# DRV8701.net
KiCad netlist of a schematic drawn in EasyEDA Pro
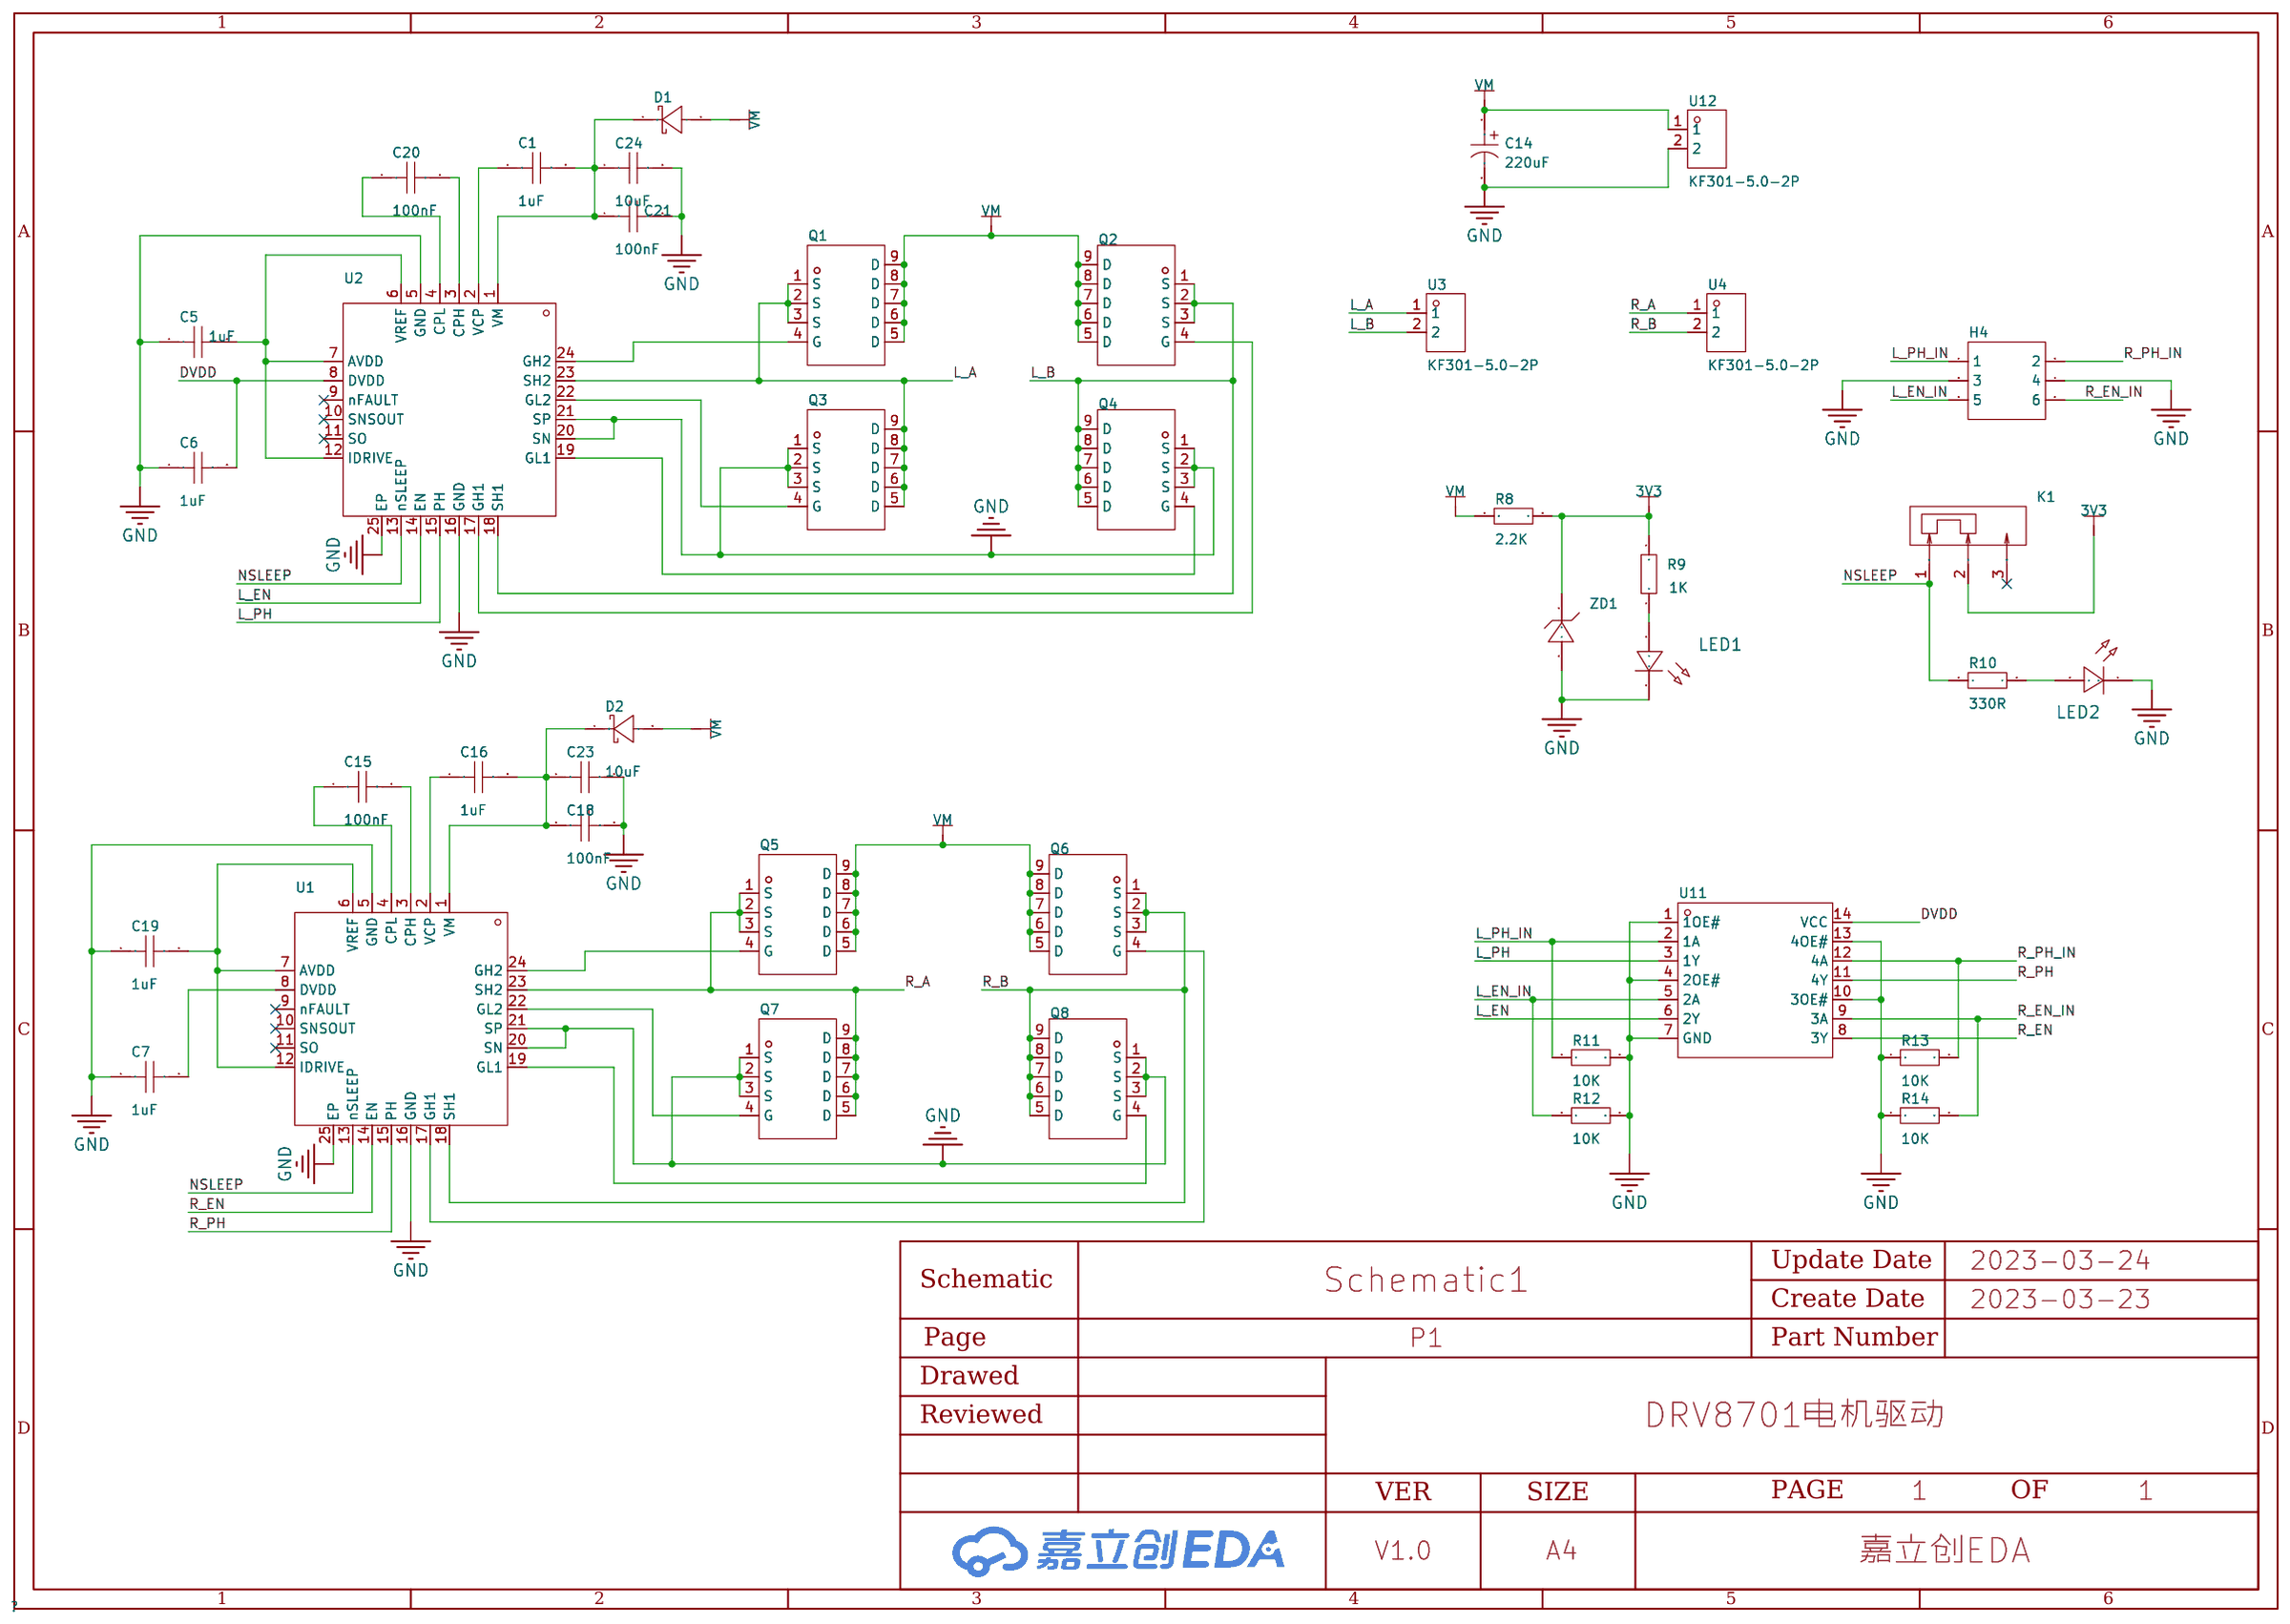
[diagram p0: schematic sheet]

(export (version "E")
  (design (tool "Eeschema 10.0.6"))
  (components
    (comp (ref "C1")
      (value "1uF")
      (footprint "easyedapro:C0805")
      (libsource (lib "easyedapro") (part "CapAcitance"))
    )
    (comp (ref "C5")
      (value "1uF")
      (footprint "easyedapro:C0805")
      (libsource (lib "easyedapro") (part "CapAcitance"))
    )
    (comp (ref "C6")
      (value "1uF")
      (footprint "easyedapro:C0805")
      (libsource (lib "easyedapro") (part "CapAcitance"))
    )
    (comp (ref "C7")
      (value "1uF")
      (footprint "easyedapro:C0805")
      (libsource (lib "easyedapro") (part "CapAcitance"))
    )
    (comp (ref "C14")
      (value "220uF")
      (footprint "easyedapro:CAP-SMD_BD6.3-L6.6-W6.6-LS7.2-FD")
      (fields
        (field (name "Manufacturer Part") "MVG 16V 220UF 6.3*7.7")
        (field (name "Manufacturer") "SAMYOUNG(韩国三莹)")
        (field (name "Tolerance") "±20%")
      )
      (libsource (lib "easyedapro") (part "MVG 16V 220UF 6.3*7.7"))
    )
    (comp (ref "C15")
      (value "100nF")
      (footprint "easyedapro:C0805")
      (libsource (lib "easyedapro") (part "CapAcitance"))
    )
    (comp (ref "C16")
      (value "1uF")
      (footprint "easyedapro:C0805")
      (libsource (lib "easyedapro") (part "CapAcitance"))
    )
    (comp (ref "C18")
      (value "100nF")
      (footprint "easyedapro:C0805")
      (libsource (lib "easyedapro") (part "CapAcitance"))
    )
    (comp (ref "C19")
      (value "1uF")
      (footprint "easyedapro:C0805")
      (libsource (lib "easyedapro") (part "CapAcitance"))
    )
    (comp (ref "C20")
      (value "100nF")
      (footprint "easyedapro:C0805")
      (libsource (lib "easyedapro") (part "CapAcitance"))
    )
    (comp (ref "C21")
      (value "100nF")
      (footprint "easyedapro:C0805")
      (libsource (lib "easyedapro") (part "CapAcitance"))
    )
    (comp (ref "C23")
      (value "10uF")
      (footprint "easyedapro:C0805")
      (libsource (lib "easyedapro") (part "CapAcitance"))
    )
    (comp (ref "C24")
      (value "10uF")
      (footprint "easyedapro:C0805")
      (libsource (lib "easyedapro") (part "CapAcitance"))
    )
    (comp (ref "D1")
      (value "1N5819WS")
      (footprint "easyedapro:SOD-323_L1.6-W1.3-LS2.7-RD")
      (description "二极管配置:独立式;直流反向耐压(Vr):40V;平均整流电流(Io):-;正向压降(Vf):600mV@200mA;反向电流(Ir):5A@30V;")
      (fields (field (name "Manufacturer") "YFW佑风微"))
      (libsource (lib "easyedapro") (part "1N5819WS_C1884554"))
    )
    (comp (ref "D2")
      (value "1N5819WS")
      (footprint "easyedapro:SOD-323_L1.6-W1.3-LS2.7-RD")
      (description "二极管配置:独立式;直流反向耐压(Vr):40V;平均整流电流(Io):-;正向压降(Vf):600mV@200mA;反向电流(Ir):5A@30V;")
      (fields (field (name "Manufacturer") "YFW佑风微"))
      (libsource (lib "easyedapro") (part "1N5819WS_C1884554"))
    )
    (comp (ref "H4")
      (value "~")
      (footprint "easyedapro:HDR-TH_6P-P2.54-V-F-R2-C3-S2.54")
      (libsource (lib "easyedapro") (part "HDR-F-2.54_2x3"))
    )
    (comp (ref "K1")
      (value "~")
      (footprint "easyedapro:SW-TH_SS-12D10-G050")
      (fields (field (name "Manufacturer Part") "SS-12D10-G5") (field (name "Manufacturer") "DEALON(德艺隆)"))
      (libsource (lib "easyedapro") (part "SS-12D10-G5"))
    )
    (comp (ref "LED1")
      (value "~")
      (footprint "easyedapro:LED0603-RD_BLUE")
      (libsource (lib "easyedapro") (part "LED_R"))
    )
    (comp (ref "LED2")
      (value "~")
      (footprint "easyedapro:LED0603-RD_BLUE")
      (libsource (lib "easyedapro") (part "LED_R"))
    )
    (comp (ref "Q1")
      (value "TPH1R403NL")
      (footprint "easyedapro:DSOP-8_L5.0-W5.0-P1.27-LS6.0-BL-EP")
      (fields (field (name "Manufacturer") "TOSHIBA(东芝)"))
      (libsource (lib "easyedapro") (part "TPH1R403NL"))
    )
    (comp (ref "Q2")
      (value "TPH1R403NL")
      (footprint "easyedapro:DSOP-8_L5.0-W5.0-P1.27-LS6.0-BL-EP")
      (fields (field (name "Manufacturer") "TOSHIBA(东芝)"))
      (libsource (lib "easyedapro") (part "TPH1R403NL"))
    )
    (comp (ref "Q3")
      (value "TPH1R403NL")
      (footprint "easyedapro:DSOP-8_L5.0-W5.0-P1.27-LS6.0-BL-EP")
      (fields (field (name "Manufacturer") "TOSHIBA(东芝)"))
      (libsource (lib "easyedapro") (part "TPH1R403NL"))
    )
    (comp (ref "Q4")
      (value "TPH1R403NL")
      (footprint "easyedapro:DSOP-8_L5.0-W5.0-P1.27-LS6.0-BL-EP")
      (fields (field (name "Manufacturer") "TOSHIBA(东芝)"))
      (libsource (lib "easyedapro") (part "TPH1R403NL"))
    )
    (comp (ref "Q5")
      (value "TPH1R403NL")
      (footprint "easyedapro:DSOP-8_L5.0-W5.0-P1.27-LS6.0-BL-EP")
      (fields (field (name "Manufacturer") "TOSHIBA(东芝)"))
      (libsource (lib "easyedapro") (part "TPH1R403NL"))
    )
    (comp (ref "Q6")
      (value "TPH1R403NL")
      (footprint "easyedapro:DSOP-8_L5.0-W5.0-P1.27-LS6.0-BL-EP")
      (fields (field (name "Manufacturer") "TOSHIBA(东芝)"))
      (libsource (lib "easyedapro") (part "TPH1R403NL"))
    )
    (comp (ref "Q7")
      (value "TPH1R403NL")
      (footprint "easyedapro:DSOP-8_L5.0-W5.0-P1.27-LS6.0-BL-EP")
      (fields (field (name "Manufacturer") "TOSHIBA(东芝)"))
      (libsource (lib "easyedapro") (part "TPH1R403NL"))
    )
    (comp (ref "Q8")
      (value "TPH1R403NL")
      (footprint "easyedapro:DSOP-8_L5.0-W5.0-P1.27-LS6.0-BL-EP")
      (fields (field (name "Manufacturer") "TOSHIBA(东芝)"))
      (libsource (lib "easyedapro") (part "TPH1R403NL"))
    )
    (comp (ref "R8") (value "2.2K") (footprint "easyedapro:R0603") (libsource (lib "easyedapro") (part "电阻")))
    (comp (ref "R9") (value "1K") (footprint "easyedapro:R0603") (libsource (lib "easyedapro") (part "电阻")))
    (comp (ref "R10")
      (value "330R")
      (footprint "easyedapro:R0603")
      (libsource (lib "easyedapro") (part "电阻"))
    )
    (comp (ref "R11") (value "10K") (footprint "easyedapro:R0603") (libsource (lib "easyedapro") (part "电阻")))
    (comp (ref "R12") (value "10K") (footprint "easyedapro:R0603") (libsource (lib "easyedapro") (part "电阻")))
    (comp (ref "R13") (value "10K") (footprint "easyedapro:R0603") (libsource (lib "easyedapro") (part "电阻")))
    (comp (ref "R14") (value "10K") (footprint "easyedapro:R0603") (libsource (lib "easyedapro") (part "电阻")))
    (comp (ref "U1")
      (value "DRV8701ERGET")
      (footprint "easyedapro:VQFN-24_L4.0-W4.0-P0.50-LS4.0-BL-EP")
      (description "DRV8701 DRV8701 H 桥栅极驱动器")
      (fields (field (name "Manufacturer") "TI(德州仪器)"))
      (libsource (lib "easyedapro") (part "DRV8701ERGET"))
    )
    (comp (ref "U2")
      (value "DRV8701ERGET")
      (footprint "easyedapro:VQFN-24_L4.0-W4.0-P0.50-LS4.0-BL-EP")
      (description "DRV8701 DRV8701 H 桥栅极驱动器")
      (fields (field (name "Manufacturer") "TI(德州仪器)"))
      (libsource (lib "easyedapro") (part "DRV8701ERGET"))
    )
    (comp (ref "U3")
      (value "KF301-5.0-2P")
      (footprint "easyedapro:CONN-TH_P5.00_KF301-5.0-2P")
      (fields (field (name "Manufacturer") "KEFA(科发)"))
      (libsource (lib "easyedapro") (part "KF301-5.0-2P"))
    )
    (comp (ref "U4")
      (value "KF301-5.0-2P")
      (footprint "easyedapro:CONN-TH_P5.00_KF301-5.0-2P")
      (fields (field (name "Manufacturer") "KEFA(科发)"))
      (libsource (lib "easyedapro") (part "KF301-5.0-2P"))
    )
    (comp (ref "U11")
      (value "SN74HC125PWR")
      (footprint "easyedapro:TSSOP-14_L5.0-W4.4-P0.65-LS6.5-BL")
      (description "逻辑电路的归属系列:74HC;逻辑类型:缓冲器，非反向;元件数:4;每元件位数:1;")
      (fields (field (name "Manufacturer") "TI(德州仪器)"))
      (libsource (lib "easyedapro") (part "SN74HC125PWR"))
    )
    (comp (ref "U12")
      (value "KF301-5.0-2P")
      (footprint "easyedapro:CONN-TH_P5.00_KF301-5.0-2P")
      (fields (field (name "Manufacturer") "KEFA(科发)"))
      (libsource (lib "easyedapro") (part "KF301-5.0-2P"))
    )
    (comp (ref "ZD1")
      (value "BZT52C3V3")
      (footprint "easyedapro:SOD-123_L2.8-W1.8-LS3.7-RD")
      (description "二极管配置:独立式;稳压值(标称值):3.3V;稳压值(范围):3.1V~3.5V;精度:-;功率:350mW;反向电流(Ir):5A@1V;阻抗(Zzt):95Ω;")
      (fields (field (name "Manufacturer") "CJ（江苏长电/长晶）"))
      (libsource (lib "easyedapro") (part "BZT52C3V3_C2112"))
    )
  )
  (nets
    (net (code "1") (name "/DVDD") (class "Default")
      (node (ref "C6") (pin "2") (pinfunction "2_2") (pintype "input"))
      (node (ref "U11") (pin "14") (pinfunction "VCC_14") (pintype "input"))
      (node (ref "U2") (pin "8") (pinfunction "DVDD_8") (pintype "input"))
    )
    (net (code "2") (name "/L_A") (class "Default")
      (node (ref "Q1") (pin "1") (pinfunction "S_1") (pintype "input"))
      (node (ref "Q1") (pin "2") (pinfunction "S_2") (pintype "input"))
      (node (ref "Q1") (pin "3") (pinfunction "S_3") (pintype "input"))
      (node (ref "Q3") (pin "5") (pinfunction "D_5") (pintype "input"))
      (node (ref "Q3") (pin "6") (pinfunction "D_6") (pintype "input"))
      (node (ref "Q3") (pin "7") (pinfunction "D_7") (pintype "input"))
      (node (ref "Q3") (pin "8") (pinfunction "D_8") (pintype "input"))
      (node (ref "Q3") (pin "9") (pinfunction "D_9") (pintype "input"))
      (node (ref "U2") (pin "23") (pinfunction "SH2_23") (pintype "input"))
      (node (ref "U3") (pin "1") (pinfunction "1_1") (pintype "input"))
    )
    (net (code "3") (name "/L_B") (class "Default")
      (node (ref "Q2") (pin "1") (pinfunction "S_1") (pintype "input"))
      (node (ref "Q2") (pin "2") (pinfunction "S_2") (pintype "input"))
      (node (ref "Q2") (pin "3") (pinfunction "S_3") (pintype "input"))
      (node (ref "Q4") (pin "5") (pinfunction "D_5") (pintype "input"))
      (node (ref "Q4") (pin "6") (pinfunction "D_6") (pintype "input"))
      (node (ref "Q4") (pin "7") (pinfunction "D_7") (pintype "input"))
      (node (ref "Q4") (pin "8") (pinfunction "D_8") (pintype "input"))
      (node (ref "Q4") (pin "9") (pinfunction "D_9") (pintype "input"))
      (node (ref "U2") (pin "18") (pinfunction "SH1_18") (pintype "input"))
      (node (ref "U3") (pin "2") (pinfunction "2_2") (pintype "input"))
    )
    (net (code "4") (name "/L_EN") (class "Default")
      (node (ref "U11") (pin "6") (pinfunction "2Y_6") (pintype "input"))
      (node (ref "U2") (pin "14") (pinfunction "EN_14") (pintype "input"))
    )
    (net (code "5") (name "/L_EN_IN") (class "Default")
      (node (ref "H4") (pin "5") (pinfunction "5_5") (pintype "input"))
      (node (ref "R12") (pin "1") (pinfunction "1_1") (pintype "input"))
      (node (ref "U11") (pin "5") (pinfunction "2A_5") (pintype "input"))
    )
    (net (code "6") (name "/L_PH") (class "Default")
      (node (ref "U11") (pin "3") (pinfunction "1Y_3") (pintype "input"))
      (node (ref "U2") (pin "15") (pinfunction "PH_15") (pintype "input"))
    )
    (net (code "7") (name "/L_PH_IN") (class "Default")
      (node (ref "H4") (pin "1") (pinfunction "1_1") (pintype "input"))
      (node (ref "R11") (pin "1") (pinfunction "1_1") (pintype "input"))
      (node (ref "U11") (pin "2") (pinfunction "1A_2") (pintype "input"))
    )
    (net (code "8") (name "/NSLEEP") (class "Default")
      (node (ref "K1") (pin "1") (pinfunction "1_1") (pintype "input"))
      (node (ref "R10") (pin "1") (pinfunction "1_1") (pintype "input"))
      (node (ref "U1") (pin "13") (pinfunction "nSLEEP_13") (pintype "input"))
      (node (ref "U2") (pin "13") (pinfunction "nSLEEP_13") (pintype "input"))
    )
    (net (code "9") (name "/R_A") (class "Default")
      (node (ref "Q5") (pin "1") (pinfunction "S_1") (pintype "input"))
      (node (ref "Q5") (pin "2") (pinfunction "S_2") (pintype "input"))
      (node (ref "Q5") (pin "3") (pinfunction "S_3") (pintype "input"))
      (node (ref "Q7") (pin "5") (pinfunction "D_5") (pintype "input"))
      (node (ref "Q7") (pin "6") (pinfunction "D_6") (pintype "input"))
      (node (ref "Q7") (pin "7") (pinfunction "D_7") (pintype "input"))
      (node (ref "Q7") (pin "8") (pinfunction "D_8") (pintype "input"))
      (node (ref "Q7") (pin "9") (pinfunction "D_9") (pintype "input"))
      (node (ref "U1") (pin "23") (pinfunction "SH2_23") (pintype "input"))
      (node (ref "U4") (pin "1") (pinfunction "1_1") (pintype "input"))
    )
    (net (code "10") (name "/R_B") (class "Default")
      (node (ref "Q6") (pin "1") (pinfunction "S_1") (pintype "input"))
      (node (ref "Q6") (pin "2") (pinfunction "S_2") (pintype "input"))
      (node (ref "Q6") (pin "3") (pinfunction "S_3") (pintype "input"))
      (node (ref "Q8") (pin "5") (pinfunction "D_5") (pintype "input"))
      (node (ref "Q8") (pin "6") (pinfunction "D_6") (pintype "input"))
      (node (ref "Q8") (pin "7") (pinfunction "D_7") (pintype "input"))
      (node (ref "Q8") (pin "8") (pinfunction "D_8") (pintype "input"))
      (node (ref "Q8") (pin "9") (pinfunction "D_9") (pintype "input"))
      (node (ref "U1") (pin "18") (pinfunction "SH1_18") (pintype "input"))
      (node (ref "U4") (pin "2") (pinfunction "2_2") (pintype "input"))
    )
    (net (code "11") (name "/R_EN") (class "Default")
      (node (ref "U1") (pin "14") (pinfunction "EN_14") (pintype "input"))
      (node (ref "U11") (pin "8") (pinfunction "3Y_8") (pintype "input"))
    )
    (net (code "12") (name "/R_EN_IN") (class "Default")
      (node (ref "H4") (pin "6") (pinfunction "6_6") (pintype "input"))
      (node (ref "R14") (pin "2") (pinfunction "2_2") (pintype "input"))
      (node (ref "U11") (pin "9") (pinfunction "3A_9") (pintype "input"))
    )
    (net (code "13") (name "/R_PH") (class "Default")
      (node (ref "U1") (pin "15") (pinfunction "PH_15") (pintype "input"))
      (node (ref "U11") (pin "11") (pinfunction "4Y_11") (pintype "input"))
    )
    (net (code "14") (name "/R_PH_IN") (class "Default")
      (node (ref "H4") (pin "2") (pinfunction "2_2") (pintype "input"))
      (node (ref "R13") (pin "2") (pinfunction "2_2") (pintype "input"))
      (node (ref "U11") (pin "12") (pinfunction "4A_12") (pintype "input"))
    )
    (net (code "15") (name "3V3") (class "Default")
      (node (ref "K1") (pin "2") (pinfunction "2_2") (pintype "input"))
      (node (ref "R8") (pin "2") (pinfunction "2_2") (pintype "input"))
      (node (ref "R9") (pin "2") (pinfunction "2_2") (pintype "input"))
      (node (ref "ZD1") (pin "1") (pinfunction "K_1") (pintype "input"))
    )
    (net (code "16") (name "GND") (class "Default")
      (node (ref "C14") (pin "2") (pinfunction "2_2") (pintype "input"))
      (node (ref "C18") (pin "2") (pinfunction "2_2") (pintype "input"))
      (node (ref "C19") (pin "1") (pinfunction "1_1") (pintype "input"))
      (node (ref "C21") (pin "2") (pinfunction "2_2") (pintype "input"))
      (node (ref "C23") (pin "2") (pinfunction "2_2") (pintype "input"))
      (node (ref "C24") (pin "2") (pinfunction "2_2") (pintype "input"))
      (node (ref "C5") (pin "1") (pinfunction "1_1") (pintype "input"))
      (node (ref "C6") (pin "1") (pinfunction "1_1") (pintype "input"))
      (node (ref "C7") (pin "1") (pinfunction "1_1") (pintype "input"))
      (node (ref "H4") (pin "3") (pinfunction "3_3") (pintype "input"))
      (node (ref "H4") (pin "4") (pinfunction "4_4") (pintype "input"))
      (node (ref "LED1") (pin "1") (pinfunction "C_1") (pintype "input"))
      (node (ref "LED2") (pin "1") (pinfunction "C_1") (pintype "input"))
      (node (ref "Q3") (pin "1") (pinfunction "S_1") (pintype "input"))
      (node (ref "Q3") (pin "2") (pinfunction "S_2") (pintype "input"))
      (node (ref "Q3") (pin "3") (pinfunction "S_3") (pintype "input"))
      (node (ref "Q4") (pin "1") (pinfunction "S_1") (pintype "input"))
      (node (ref "Q4") (pin "2") (pinfunction "S_2") (pintype "input"))
      (node (ref "Q4") (pin "3") (pinfunction "S_3") (pintype "input"))
      (node (ref "Q7") (pin "1") (pinfunction "S_1") (pintype "input"))
      (node (ref "Q7") (pin "2") (pinfunction "S_2") (pintype "input"))
      (node (ref "Q7") (pin "3") (pinfunction "S_3") (pintype "input"))
      (node (ref "Q8") (pin "1") (pinfunction "S_1") (pintype "input"))
      (node (ref "Q8") (pin "2") (pinfunction "S_2") (pintype "input"))
      (node (ref "Q8") (pin "3") (pinfunction "S_3") (pintype "input"))
      (node (ref "R11") (pin "2") (pinfunction "2_2") (pintype "input"))
      (node (ref "R12") (pin "2") (pinfunction "2_2") (pintype "input"))
      (node (ref "R13") (pin "1") (pinfunction "1_1") (pintype "input"))
      (node (ref "R14") (pin "1") (pinfunction "1_1") (pintype "input"))
      (node (ref "U1") (pin "16") (pinfunction "GND_16") (pintype "input"))
      (node (ref "U1") (pin "20") (pinfunction "SN_20") (pintype "input"))
      (node (ref "U1") (pin "21") (pinfunction "SP_21") (pintype "input"))
      (node (ref "U1") (pin "25") (pinfunction "EP_25") (pintype "input"))
      (node (ref "U1") (pin "5") (pinfunction "GND_5") (pintype "input"))
      (node (ref "U11") (pin "1") (pinfunction "1OE#_1") (pintype "input"))
      (node (ref "U11") (pin "10") (pinfunction "3OE#_10") (pintype "input"))
      (node (ref "U11") (pin "13") (pinfunction "4OE#_13") (pintype "input"))
      (node (ref "U11") (pin "4") (pinfunction "2OE#_4") (pintype "input"))
      (node (ref "U11") (pin "7") (pinfunction "GND_7") (pintype "input"))
      (node (ref "U12") (pin "2") (pinfunction "2_2") (pintype "input"))
      (node (ref "U2") (pin "16") (pinfunction "GND_16") (pintype "input"))
      (node (ref "U2") (pin "20") (pinfunction "SN_20") (pintype "input"))
      (node (ref "U2") (pin "21") (pinfunction "SP_21") (pintype "input"))
      (node (ref "U2") (pin "25") (pinfunction "EP_25") (pintype "input"))
      (node (ref "U2") (pin "5") (pinfunction "GND_5") (pintype "input"))
      (node (ref "ZD1") (pin "2") (pinfunction "A_2") (pintype "input"))
    )
    (net (code "17") (name "Net-(D1-C)") (class "Default")
      (node (ref "C1") (pin "2") (pinfunction "2_2") (pintype "input"))
      (node (ref "C21") (pin "1") (pinfunction "1_1") (pintype "input"))
      (node (ref "C24") (pin "1") (pinfunction "1_1") (pintype "input"))
      (node (ref "D1") (pin "1") (pinfunction "C_1") (pintype "input"))
      (node (ref "U2") (pin "1") (pinfunction "VM_1") (pintype "input"))
    )
    (net (code "18") (name "Net-(D2-C)") (class "Default")
      (node (ref "C16") (pin "2") (pinfunction "2_2") (pintype "input"))
      (node (ref "C18") (pin "1") (pinfunction "1_1") (pintype "input"))
      (node (ref "C23") (pin "1") (pinfunction "1_1") (pintype "input"))
      (node (ref "D2") (pin "1") (pinfunction "C_1") (pintype "input"))
      (node (ref "U1") (pin "1") (pinfunction "VM_1") (pintype "input"))
    )
    (net (code "19") (name "Net-(LED1-A)") (class "Default")
      (node (ref "LED1") (pin "2") (pinfunction "A_2") (pintype "input"))
      (node (ref "R9") (pin "1") (pinfunction "1_1") (pintype "input"))
    )
    (net (code "20") (name "Net-(LED2-A)") (class "Default")
      (node (ref "LED2") (pin "2") (pinfunction "A_2") (pintype "input"))
      (node (ref "R10") (pin "2") (pinfunction "2_2") (pintype "input"))
    )
    (net (code "21") (name "Net-(Q1-G)") (class "Default")
      (node (ref "Q1") (pin "4") (pinfunction "G_4") (pintype "input"))
      (node (ref "U2") (pin "24") (pinfunction "GH2_24") (pintype "input"))
    )
    (net (code "22") (name "Net-(Q2-G)") (class "Default")
      (node (ref "Q2") (pin "4") (pinfunction "G_4") (pintype "input"))
      (node (ref "U2") (pin "17") (pinfunction "GH1_17") (pintype "input"))
    )
    (net (code "23") (name "Net-(Q3-G)") (class "Default")
      (node (ref "Q3") (pin "4") (pinfunction "G_4") (pintype "input"))
      (node (ref "U2") (pin "22") (pinfunction "GL2_22") (pintype "input"))
    )
    (net (code "24") (name "Net-(Q4-G)") (class "Default")
      (node (ref "Q4") (pin "4") (pinfunction "G_4") (pintype "input"))
      (node (ref "U2") (pin "19") (pinfunction "GL1_19") (pintype "input"))
    )
    (net (code "25") (name "Net-(Q5-G)") (class "Default")
      (node (ref "Q5") (pin "4") (pinfunction "G_4") (pintype "input"))
      (node (ref "U1") (pin "24") (pinfunction "GH2_24") (pintype "input"))
    )
    (net (code "26") (name "Net-(Q6-G)") (class "Default")
      (node (ref "Q6") (pin "4") (pinfunction "G_4") (pintype "input"))
      (node (ref "U1") (pin "17") (pinfunction "GH1_17") (pintype "input"))
    )
    (net (code "27") (name "Net-(Q7-G)") (class "Default")
      (node (ref "Q7") (pin "4") (pinfunction "G_4") (pintype "input"))
      (node (ref "U1") (pin "22") (pinfunction "GL2_22") (pintype "input"))
    )
    (net (code "28") (name "Net-(Q8-G)") (class "Default")
      (node (ref "Q8") (pin "4") (pinfunction "G_4") (pintype "input"))
      (node (ref "U1") (pin "19") (pinfunction "GL1_19") (pintype "input"))
    )
    (net (code "29") (name "Net-(U1-AVDD)") (class "Default")
      (node (ref "C19") (pin "2") (pinfunction "2_2") (pintype "input"))
      (node (ref "U1") (pin "12") (pinfunction "IDRIVE_12") (pintype "input"))
      (node (ref "U1") (pin "6") (pinfunction "VREF_6") (pintype "input"))
      (node (ref "U1") (pin "7") (pinfunction "AVDD_7") (pintype "input"))
    )
    (net (code "30") (name "Net-(U1-CPH)") (class "Default")
      (node (ref "C15") (pin "2") (pinfunction "2_2") (pintype "input"))
      (node (ref "U1") (pin "3") (pinfunction "CPH_3") (pintype "input"))
    )
    (net (code "31") (name "Net-(U1-CPL)") (class "Default")
      (node (ref "C15") (pin "1") (pinfunction "1_1") (pintype "input"))
      (node (ref "U1") (pin "4") (pinfunction "CPL_4") (pintype "input"))
    )
    (net (code "32") (name "Net-(U1-DVDD)") (class "Default")
      (node (ref "C7") (pin "2") (pinfunction "2_2") (pintype "input"))
      (node (ref "U1") (pin "8") (pinfunction "DVDD_8") (pintype "input"))
    )
    (net (code "33") (name "Net-(U1-VCP)") (class "Default")
      (node (ref "C16") (pin "1") (pinfunction "1_1") (pintype "input"))
      (node (ref "U1") (pin "2") (pinfunction "VCP_2") (pintype "input"))
    )
    (net (code "34") (name "Net-(U2-AVDD)") (class "Default")
      (node (ref "C5") (pin "2") (pinfunction "2_2") (pintype "input"))
      (node (ref "U2") (pin "12") (pinfunction "IDRIVE_12") (pintype "input"))
      (node (ref "U2") (pin "6") (pinfunction "VREF_6") (pintype "input"))
      (node (ref "U2") (pin "7") (pinfunction "AVDD_7") (pintype "input"))
    )
    (net (code "35") (name "Net-(U2-CPH)") (class "Default")
      (node (ref "C20") (pin "2") (pinfunction "2_2") (pintype "input"))
      (node (ref "U2") (pin "3") (pinfunction "CPH_3") (pintype "input"))
    )
    (net (code "36") (name "Net-(U2-CPL)") (class "Default")
      (node (ref "C20") (pin "1") (pinfunction "1_1") (pintype "input"))
      (node (ref "U2") (pin "4") (pinfunction "CPL_4") (pintype "input"))
    )
    (net (code "37") (name "Net-(U2-VCP)") (class "Default")
      (node (ref "C1") (pin "1") (pinfunction "1_1") (pintype "input"))
      (node (ref "U2") (pin "2") (pinfunction "VCP_2") (pintype "input"))
    )
    (net (code "38") (name "VM") (class "Default")
      (node (ref "C14") (pin "1") (pinfunction "1_1") (pintype "input"))
      (node (ref "D1") (pin "2") (pinfunction "A_2") (pintype "input"))
      (node (ref "D2") (pin "2") (pinfunction "A_2") (pintype "input"))
      (node (ref "Q1") (pin "5") (pinfunction "D_5") (pintype "input"))
      (node (ref "Q1") (pin "6") (pinfunction "D_6") (pintype "input"))
      (node (ref "Q1") (pin "7") (pinfunction "D_7") (pintype "input"))
      (node (ref "Q1") (pin "8") (pinfunction "D_8") (pintype "input"))
      (node (ref "Q1") (pin "9") (pinfunction "D_9") (pintype "input"))
      (node (ref "Q2") (pin "5") (pinfunction "D_5") (pintype "input"))
      (node (ref "Q2") (pin "6") (pinfunction "D_6") (pintype "input"))
      (node (ref "Q2") (pin "7") (pinfunction "D_7") (pintype "input"))
      (node (ref "Q2") (pin "8") (pinfunction "D_8") (pintype "input"))
      (node (ref "Q2") (pin "9") (pinfunction "D_9") (pintype "input"))
      (node (ref "Q5") (pin "5") (pinfunction "D_5") (pintype "input"))
      (node (ref "Q5") (pin "6") (pinfunction "D_6") (pintype "input"))
      (node (ref "Q5") (pin "7") (pinfunction "D_7") (pintype "input"))
      (node (ref "Q5") (pin "8") (pinfunction "D_8") (pintype "input"))
      (node (ref "Q5") (pin "9") (pinfunction "D_9") (pintype "input"))
      (node (ref "Q6") (pin "5") (pinfunction "D_5") (pintype "input"))
      (node (ref "Q6") (pin "6") (pinfunction "D_6") (pintype "input"))
      (node (ref "Q6") (pin "7") (pinfunction "D_7") (pintype "input"))
      (node (ref "Q6") (pin "8") (pinfunction "D_8") (pintype "input"))
      (node (ref "Q6") (pin "9") (pinfunction "D_9") (pintype "input"))
      (node (ref "R8") (pin "1") (pinfunction "1_1") (pintype "input"))
      (node (ref "U12") (pin "1") (pinfunction "1_1") (pintype "input"))
    )
    (net (code "39") (name "unconnected-(K1-Pad3)") (class "Default")
      (node (ref "K1") (pin "3") (pinfunction "3_3") (pintype "input+no_connect"))
    )
    (net (code "40") (name "unconnected-(U1-SNSOUT-Pad10)") (class "Default")
      (node (ref "U1") (pin "10") (pinfunction "SNSOUT_10") (pintype "input+no_connect"))
    )
    (net (code "41") (name "unconnected-(U1-SO-Pad11)") (class "Default")
      (node (ref "U1") (pin "11") (pinfunction "SO_11") (pintype "input+no_connect"))
    )
    (net (code "42") (name "unconnected-(U1-nFAULT-Pad9)") (class "Default")
      (node (ref "U1") (pin "9") (pinfunction "nFAULT_9") (pintype "input+no_connect"))
    )
    (net (code "43") (name "unconnected-(U2-SNSOUT-Pad10)") (class "Default")
      (node (ref "U2") (pin "10") (pinfunction "SNSOUT_10") (pintype "input+no_connect"))
    )
    (net (code "44") (name "unconnected-(U2-SO-Pad11)") (class "Default")
      (node (ref "U2") (pin "11") (pinfunction "SO_11") (pintype "input+no_connect"))
    )
    (net (code "45") (name "unconnected-(U2-nFAULT-Pad9)") (class "Default")
      (node (ref "U2") (pin "9") (pinfunction "nFAULT_9") (pintype "input+no_connect"))
    )
  )
)
